# rapidshark_mark_6_12.net
KiCad netlist of a schematic drawn in EAGLE
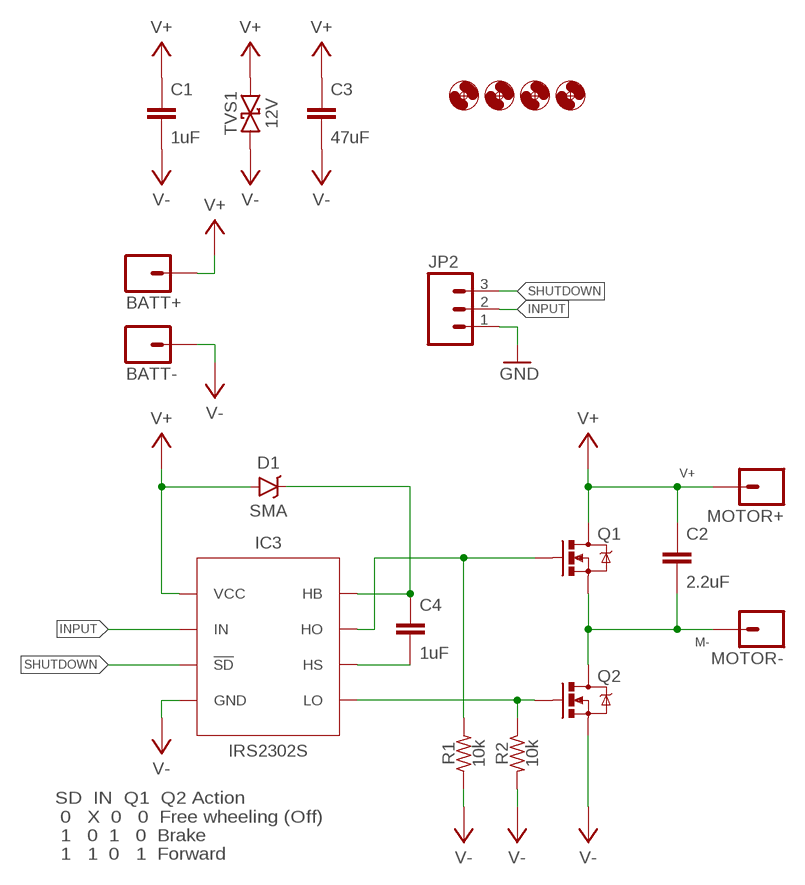
[diagram p0: schematic, sheet 1]

(export (version "E")
  (design (tool "Eeschema 10.0.6"))
  (components
    (comp (ref "BATT+")
      (value "M01PTH_2MM")
      (footprint "eagle-import:1X01_2MM")
      (libsource (lib "eagle-import") (part "M01PTH_2MM"))
    )
    (comp (ref "BATT-")
      (value "M01PTH_2MM")
      (footprint "eagle-import:1X01_2MM")
      (libsource (lib "eagle-import") (part "M01PTH_2MM"))
    )
    (comp (ref "C1")
      (value "1uF")
      (footprint "eagle-import:C0805")
      (libsource (lib "eagle-import") (part "CAPACITOR-CERAMICC0805"))
    )
    (comp (ref "C2")
      (value "2.2uF")
      (footprint "eagle-import:C0805")
      (libsource (lib "eagle-import") (part "CAPACITOR-CERAMICC0805"))
    )
    (comp (ref "C3")
      (value "47uF")
      (footprint "eagle-import:C1206")
      (libsource (lib "eagle-import") (part "CAPACITOR-CERAMICC1206"))
    )
    (comp (ref "C4")
      (value "1uF")
      (footprint "eagle-import:C0805")
      (libsource (lib "eagle-import") (part "CAPACITOR-CERAMICC0805"))
    )
    (comp (ref "D1")
      (value "SMA")
      (footprint "eagle-import:SMA-DIODE-SCHOTTKY")
      (libsource (lib "eagle-import") (part "DIODE-SCHOTTKYSMA"))
    )
    (comp (ref "H1")
      (value "HOLE#2")
      (footprint "eagle-import:HOLE-#2")
      (libsource (lib "eagle-import") (part "HOLE#2"))
    )
    (comp (ref "H2")
      (value "HOLE#2")
      (footprint "eagle-import:HOLE-#2")
      (libsource (lib "eagle-import") (part "HOLE#2"))
    )
    (comp (ref "H3")
      (value "HOLE#2")
      (footprint "eagle-import:HOLE-#2")
      (libsource (lib "eagle-import") (part "HOLE#2"))
    )
    (comp (ref "H4")
      (value "HOLE#2")
      (footprint "eagle-import:HOLE-#2")
      (libsource (lib "eagle-import") (part "HOLE#2"))
    )
    (comp (ref "IC3")
      (value "IRS2302S")
      (footprint "eagle-import:SO08")
      (libsource (lib "eagle-import") (part "IRS2302S"))
    )
    (comp (ref "JP2")
      (value "M03PTH")
      (footprint "eagle-import:1X03")
      (libsource (lib "eagle-import") (part "M03PTH"))
    )
    (comp (ref "MOTOR+")
      (value "M01PTH_2MM")
      (footprint "eagle-import:1X01_2MM")
      (libsource (lib "eagle-import") (part "M01PTH_2MM"))
    )
    (comp (ref "MOTOR-")
      (value "M01PTH_2MM")
      (footprint "eagle-import:1X01_2MM")
      (libsource (lib "eagle-import") (part "M01PTH_2MM"))
    )
    (comp (ref "Q1")
      (value "MOSFET-NCHANNELPSMN4R0-30YLD")
      (footprint "eagle-import:LFPAK56")
      (libsource (lib "eagle-import") (part "MOSFET-NCHANNELPSMN4R0-30YLD"))
    )
    (comp (ref "Q2")
      (value "MOSFET-NCHANNELPSMN4R0-30YLD")
      (footprint "eagle-import:LFPAK56")
      (libsource (lib "eagle-import") (part "MOSFET-NCHANNELPSMN4R0-30YLD"))
    )
    (comp (ref "R1")
      (value "10k")
      (footprint "eagle-import:R0805")
      (libsource (lib "eagle-import") (part "RESISTORR0805"))
    )
    (comp (ref "R2")
      (value "10k")
      (footprint "eagle-import:R0805")
      (libsource (lib "eagle-import") (part "RESISTORR0805"))
    )
    (comp (ref "TVS1")
      (value "12V")
      (footprint "eagle-import:SMA-DIODE-TVS-BIDIR")
      (libsource (lib "eagle-import") (part "TVSSMA"))
    )
  )
  (nets
    (net (code "1") (name "/M-") (class "Default")
      (node (ref "C2") (pin "2") (pinfunction "2_2") (pintype "passive"))
      (node (ref "MOTOR-") (pin "1") (pinfunction "1_1") (pintype "passive"))
      (node (ref "Q1") (pin "1") (pinfunction "S_1") (pintype "passive"))
      (node (ref "Q1") (pin "2") (pinfunction "S_2") (pintype "passive"))
      (node (ref "Q1") (pin "3") (pinfunction "S_3") (pintype "passive"))
      (node (ref "Q2") (pin "MB@1") (pinfunction "D_MB@1") (pintype "passive"))
      (node (ref "Q2") (pin "MB@2") (pinfunction "D_MB@2") (pintype "passive"))
    )
    (net (code "2") (name "GND") (class "Default")
      (node (ref "JP2") (pin "1") (pinfunction "1_1") (pintype "passive"))
    )
    (net (code "3") (name "INPUT") (class "Default")
      (node (ref "IC3") (pin "2") (pinfunction "IN_2") (pintype "passive"))
      (node (ref "JP2") (pin "2") (pinfunction "2_2") (pintype "passive"))
    )
    (net (code "4") (name "Net-(IC3-HB)") (class "Default")
      (node (ref "C4") (pin "1") (pinfunction "1_1") (pintype "passive"))
      (node (ref "D1") (pin "C") (pinfunction "C_C") (pintype "passive"))
      (node (ref "IC3") (pin "8") (pinfunction "HB_8") (pintype "passive"))
    )
    (net (code "5") (name "Net-(IC3-HO)") (class "Default")
      (node (ref "IC3") (pin "7") (pinfunction "HO_7") (pintype "passive"))
      (node (ref "Q1") (pin "4") (pinfunction "G_4") (pintype "passive"))
      (node (ref "R1") (pin "2") (pinfunction "2_2") (pintype "passive"))
    )
    (net (code "6") (name "Net-(IC3-HS)") (class "Default")
      (node (ref "C4") (pin "2") (pinfunction "2_2") (pintype "passive"))
      (node (ref "IC3") (pin "6") (pinfunction "HS_6") (pintype "passive"))
    )
    (net (code "7") (name "Net-(IC3-LO)") (class "Default")
      (node (ref "IC3") (pin "5") (pinfunction "LO_5") (pintype "passive"))
      (node (ref "Q2") (pin "4") (pinfunction "G_4") (pintype "passive"))
      (node (ref "R2") (pin "1") (pinfunction "1_1") (pintype "passive"))
    )
    (net (code "8") (name "SHUTDOWN") (class "Default")
      (node (ref "IC3") (pin "3") (pinfunction "~{SD}_3") (pintype "passive"))
      (node (ref "JP2") (pin "3") (pinfunction "3_3") (pintype "passive"))
    )
    (net (code "9") (name "V+") (class "Default")
      (node (ref "BATT+") (pin "1") (pinfunction "1_1") (pintype "passive"))
      (node (ref "C1") (pin "1") (pinfunction "1_1") (pintype "passive"))
      (node (ref "C2") (pin "1") (pinfunction "1_1") (pintype "passive"))
      (node (ref "C3") (pin "1") (pinfunction "1_1") (pintype "passive"))
      (node (ref "D1") (pin "A") (pinfunction "A_A") (pintype "passive"))
      (node (ref "IC3") (pin "1") (pinfunction "VCC_1") (pintype "passive"))
      (node (ref "MOTOR+") (pin "1") (pinfunction "1_1") (pintype "passive"))
      (node (ref "Q1") (pin "MB@1") (pinfunction "D_MB@1") (pintype "passive"))
      (node (ref "Q1") (pin "MB@2") (pinfunction "D_MB@2") (pintype "passive"))
      (node (ref "TVS1") (pin "1") (pinfunction "1_1") (pintype "passive"))
    )
    (net (code "10") (name "V-") (class "Default")
      (node (ref "BATT-") (pin "1") (pinfunction "1_1") (pintype "passive"))
      (node (ref "C1") (pin "2") (pinfunction "2_2") (pintype "passive"))
      (node (ref "C3") (pin "2") (pinfunction "2_2") (pintype "passive"))
      (node (ref "IC3") (pin "4") (pinfunction "GND_4") (pintype "passive"))
      (node (ref "Q2") (pin "1") (pinfunction "S_1") (pintype "passive"))
      (node (ref "Q2") (pin "2") (pinfunction "S_2") (pintype "passive"))
      (node (ref "Q2") (pin "3") (pinfunction "S_3") (pintype "passive"))
      (node (ref "R1") (pin "1") (pinfunction "1_1") (pintype "passive"))
      (node (ref "R2") (pin "2") (pinfunction "2_2") (pintype "passive"))
      (node (ref "TVS1") (pin "2") (pinfunction "2_2") (pintype "passive"))
    )
  )
)
